# Temperature_and_Fan.net
KiCad netlist of a schematic drawn in Altium Designer
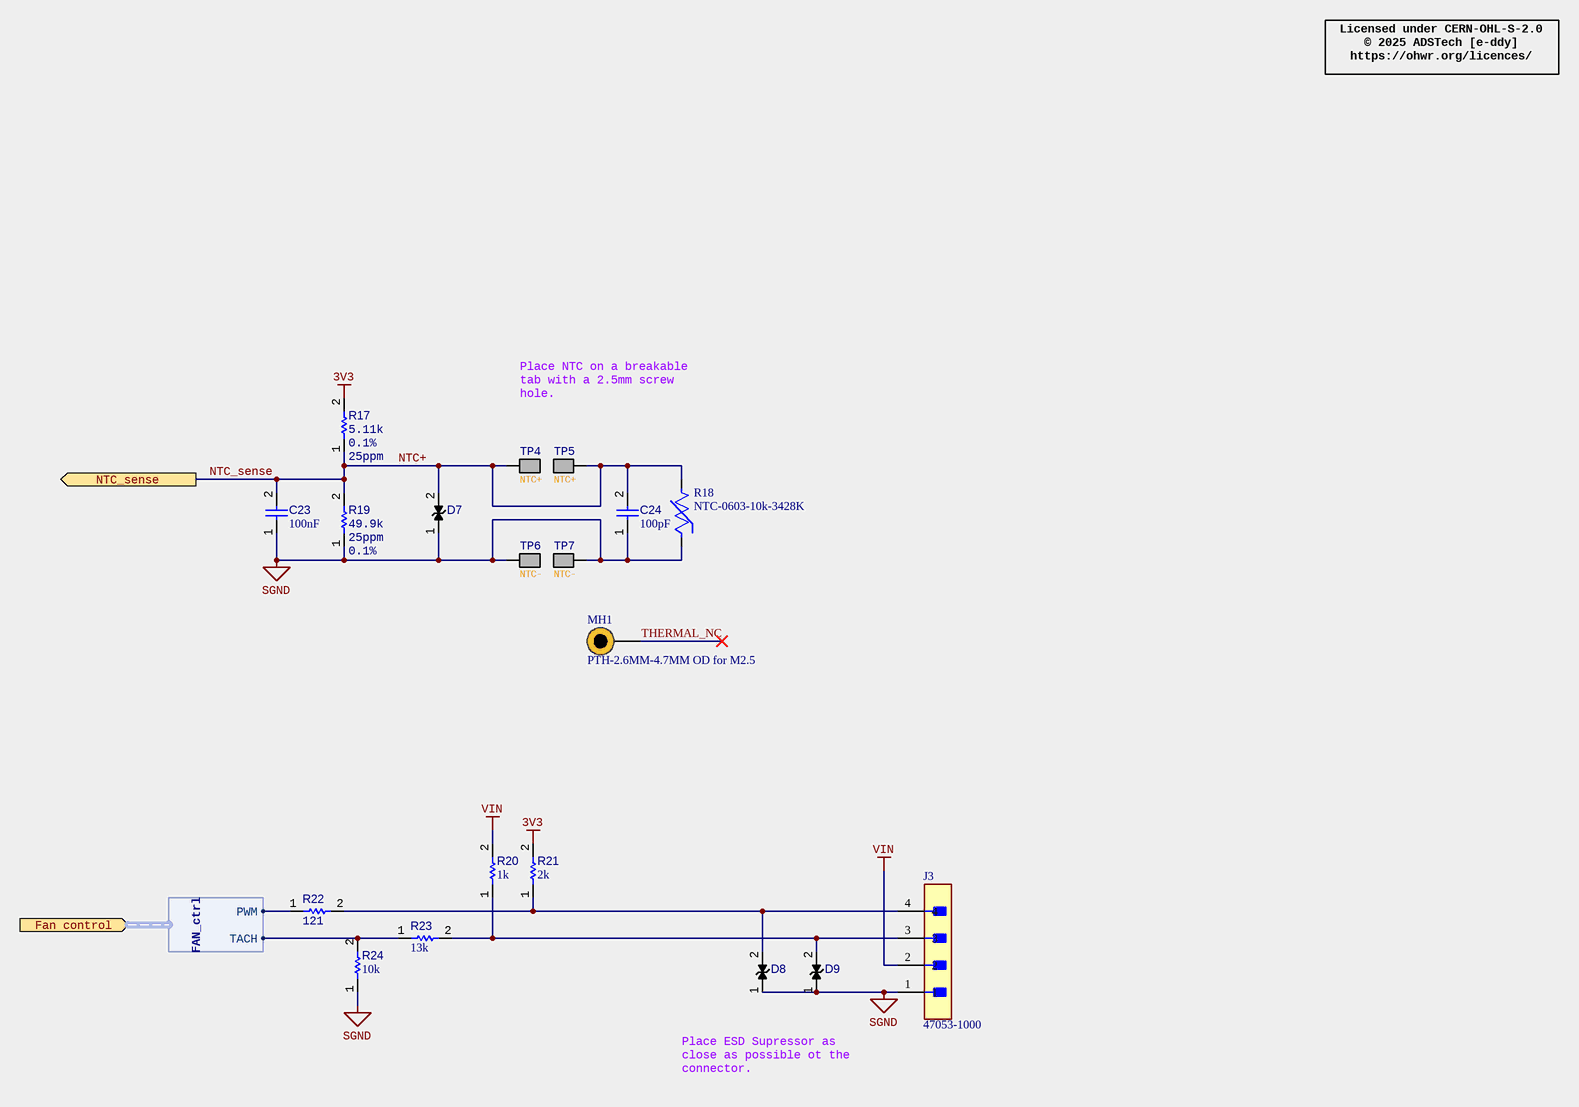
[diagram p0: Temperature and Fan.SchDoc]

(export (version "E")
  (design (tool "Eeschema 10.0.6"))
  (components
    (comp (ref "C23")
      (value "100nF")
      (footprint "CAP_0402-IPC_B")
      (description "Multilayer Ceramic Capacitor, 0.1 uF, 50 V, ± 10%, X7R, 0402 [1005 Metric]")
      (fields (field (name "TOLERANCE") "10%") (field (name "Comment") "C-0402-CER-X7R-100nF-10%-50V"))
      (libsource (lib "FIME Lille") (part "CAP-NP-2"))
    )
    (comp (ref "C24")
      (value "100pF")
      (footprint "CAP_0402-IPC_B")
      (description "Multilayer Ceramic Capacitors MLCC - SMD/SMT 50V 100pF C0G 0402 +/-1%")
      (fields (field (name "TOLERANCE") "1%") (field (name "Comment") "C-0402-C0G-100pF-50V-1%"))
      (libsource (lib "FIME Lille") (part "CAP-NP-2"))
    )
    (comp (ref "D7")
      (value "ESD-0603ESDA-MLP1")
      (footprint "CAP-0603-IPC_B")
      (description "Suppressor Esd 0.05PF 0603 SMD")
      (libsource (lib "FIME Lille") (part "ESD Suppressor"))
    )
    (comp (ref "D8")
      (value "ESD-0603ESDA-MLP1")
      (footprint "CAP-0603-IPC_B")
      (description "Suppressor Esd 0.05PF 0603 SMD")
      (libsource (lib "FIME Lille") (part "ESD Suppressor"))
    )
    (comp (ref "D9")
      (value "ESD-0603ESDA-MLP1")
      (footprint "CAP-0603-IPC_B")
      (description "Suppressor Esd 0.05PF 0603 SMD")
      (libsource (lib "FIME Lille") (part "ESD Suppressor"))
    )
    (comp (ref "J3")
      (value "47053-1000")
      (footprint "FP-470531000-MFG")
      (description "CONN HEADER VERT 4POS 2.54MM")
      (libsource (lib "Altium Content Vault") (part "299a8cea1bdcbc3624fe62c390fa72c"))
    )
    (comp (ref "MH1")
      (value "PTH-2.6MM-4.7MM OD for M2.5")
      (footprint "PTH-2.6MM-4.7MM")
      (description "2.6mm/4.7mm PLATED TROUGH HOLE. For M2.5 Cylindrical hex screw head")
      (libsource (lib "FIME Lille") (part "PTH-3.175MM"))
    )
    (comp (ref "R17")
      (value "5.11k")
      (footprint "RES-0402-IPC_B")
      (description "0402 5110.0 Ω 0.1% 25ppm 0.016W Resistor")
      (fields
        (field (name "TOLERANCE") "0.1%")
        (field (name "POWER") "16mW")
        (field (name "TCR") "25ppm")
        (field (name "Comment") "R-0402-5110.0-0.1%-25ppm-0.016")
      )
      (libsource (lib "FIME Lille") (part "RES-2"))
    )
    (comp (ref "R18")
      (value "NTC-0603-10k-3428K")
      (footprint "FP-NCU18-0_15-MFG")
      (description "NTC Thermistor, 10000ohm, Surface Mount")
      (fields (field (name "POWER") "100mW") (field (name "TOLERANCE") "1%"))
      (libsource (lib "FIME Lille") (part "3b148a6ebabc5fb4d708a66c052d352"))
    )
    (comp (ref "R19")
      (value "49.9k")
      (footprint "RES-0402-IPC_B")
      (description "0402 49900.0 Ω 0.1% 25ppm 0.016W Resistor")
      (fields
        (field (name "POWER") "16mW")
        (field (name "TCR") "25ppm")
        (field (name "TOLERANCE") "0.1%")
        (field (name "Comment") "R-0402-49900.0-0.1%-25ppm-0.016")
      )
      (libsource (lib "FIME Lille") (part "RES-2"))
    )
    (comp (ref "R20")
      (value "1k")
      (footprint "RES-0402-IPC_B")
      (description "0402 1000.0 Ω 1% 100ppm 0.063W Resistor")
      (fields (field (name "TOLERANCE") "1%") (field (name "MPN") "CRCW04021K00FKED"))
      (libsource (lib "FIME Lille") (part "RES-2"))
    )
    (comp (ref "R21")
      (value "2k")
      (footprint "RES-0402-IPC_B")
      (description "0402 2000.0 Ω 1% 100ppm 0.063W Resistor")
      (fields (field (name "POWER") "63mW") (field (name "MPN") "CRCW04022K00FKED"))
      (libsource (lib "FIME Lille") (part "RES-2"))
    )
    (comp (ref "R22")
      (value "121")
      (footprint "RES-0402-IPC_B")
      (description "0402 121.0 Ω 1% 100ppm 0.063W Resistor")
      (fields (field (name "TOLERANCE") "1%") (field (name "MPN") "CRCW0402121RFKED"))
      (libsource (lib "FIME Lille") (part "RES-2"))
    )
    (comp (ref "R23")
      (value "13k")
      (footprint "RES-0402-IPC_B")
      (description "0402 13000.0 Ω 1% 100ppm 0.063W Resistor")
      (fields (field (name "MPN") "CRCW040213K0FKED") (field (name "TOLERANCE") "1%"))
      (libsource (lib "FIME Lille") (part "RES-2"))
    )
    (comp (ref "R24")
      (value "10k")
      (footprint "RES-0402-IPC_B")
      (description "0402 10000.0 Ω 1% 100ppm 0.063W Resistor")
      (fields (field (name "MPN") "RC0402FR-0710KL") (field (name "TOLERANCE") "1%"))
      (libsource (lib "FIME Lille") (part "RES-2"))
    )
    (comp (ref "TP4")
      (value "SMT-PAD-3x2")
      (footprint "3x2 pad")
      (description "3x2mm standard pad for wire soldering")
      (fields (field (name "NAME") "NTC+"))
      (libsource (lib "FIME Lille") (part "Copy of Test point"))
    )
    (comp (ref "TP5")
      (value "SMT-PAD-3x2")
      (footprint "3x2 pad")
      (description "3x2mm standard pad for wire soldering")
      (fields (field (name "NAME") "NTC+"))
      (libsource (lib "") (part "Copy of Test point_1"))
    )
    (comp (ref "TP6")
      (value "SMT-PAD-3x2")
      (footprint "3x2 pad")
      (description "3x2mm standard pad for wire soldering")
      (fields (field (name "NAME") "NTC-"))
      (libsource (lib "FIME Lille") (part "Copy of Test point"))
    )
    (comp (ref "TP7")
      (value "SMT-PAD-3x2")
      (footprint "3x2 pad")
      (description "3x2mm standard pad for wire soldering")
      (fields (field (name "NAME") "NTC-"))
      (libsource (lib "") (part "Copy of Test point_1"))
    )
  )
  (nets
    (net (code "2") (name "/NTC+") (class "Default")
      (node (ref "C23") (pin "2") (pinfunction "2_2") (pintype "passive"))
      (node (ref "C24") (pin "2") (pinfunction "2_2") (pintype "passive"))
      (node (ref "D7") (pin "2") (pinfunction "A_2") (pintype "passive"))
      (node (ref "R17") (pin "1") (pinfunction "1_1") (pintype "passive"))
      (node (ref "R18") (pin "2") (pinfunction "2_2") (pintype "passive"))
      (node (ref "R19") (pin "2") (pinfunction "2_2") (pintype "passive"))
      (node (ref "TP4") (pin "1") (pinfunction "1_1") (pintype "passive"))
      (node (ref "TP5") (pin "1") (pinfunction "1_1") (pintype "passive"))
    )
    (net (code "3") (name "/PWM") (class "Default")
      (node (ref "R22") (pin "1") (pinfunction "1_1") (pintype "passive"))
    )
    (net (code "4") (name "/TACH") (class "Default")
      (node (ref "R23") (pin "1") (pinfunction "1_1") (pintype "passive"))
      (node (ref "R24") (pin "2") (pinfunction "2_2") (pintype "passive"))
    )
    (net (code "5") (name "/THERMAL_NC") (class "Default")
      (node (ref "MH1") (pin "0") (pinfunction "0_0") (pintype "passive+no_connect"))
    )
    (net (code "7") (name "3V3") (class "Default")
      (node (ref "R17") (pin "2") (pinfunction "2_2") (pintype "passive"))
      (node (ref "R21") (pin "2") (pinfunction "2_2") (pintype "passive"))
    )
    (net (code "8") (name "Net-(D8-A)") (class "Default")
      (node (ref "D8") (pin "2") (pinfunction "A_2") (pintype "passive"))
      (node (ref "J3") (pin "4") (pinfunction "4_4") (pintype "passive"))
      (node (ref "R21") (pin "1") (pinfunction "1_1") (pintype "passive"))
      (node (ref "R22") (pin "2") (pinfunction "2_2") (pintype "passive"))
    )
    (net (code "9") (name "Net-(D9-A)") (class "Default")
      (node (ref "D9") (pin "2") (pinfunction "A_2") (pintype "passive"))
      (node (ref "J3") (pin "3") (pinfunction "3_3") (pintype "passive"))
      (node (ref "R20") (pin "1") (pinfunction "1_1") (pintype "passive"))
      (node (ref "R23") (pin "2") (pinfunction "2_2") (pintype "passive"))
    )
    (net (code "10") (name "SGND") (class "Default")
      (node (ref "C23") (pin "1") (pinfunction "1_1") (pintype "passive"))
      (node (ref "C24") (pin "1") (pinfunction "1_1") (pintype "passive"))
      (node (ref "D7") (pin "1") (pinfunction "K_1") (pintype "passive"))
      (node (ref "D8") (pin "1") (pinfunction "K_1") (pintype "passive"))
      (node (ref "D9") (pin "1") (pinfunction "K_1") (pintype "passive"))
      (node (ref "J3") (pin "1") (pinfunction "1_1") (pintype "passive"))
      (node (ref "R18") (pin "1") (pinfunction "1_1") (pintype "passive"))
      (node (ref "R19") (pin "1") (pinfunction "1_1") (pintype "passive"))
      (node (ref "R24") (pin "1") (pinfunction "1_1") (pintype "passive"))
      (node (ref "TP6") (pin "1") (pinfunction "1_1") (pintype "passive"))
      (node (ref "TP7") (pin "1") (pinfunction "1_1") (pintype "passive"))
    )
    (net (code "11") (name "VIN") (class "Default")
      (node (ref "J3") (pin "2") (pinfunction "2_2") (pintype "passive"))
      (node (ref "R20") (pin "2") (pinfunction "2_2") (pintype "passive"))
    )
  )
)
